# ItsyBitsy_Expander_v1_1.net
KiCad netlist of a schematic drawn in EAGLE
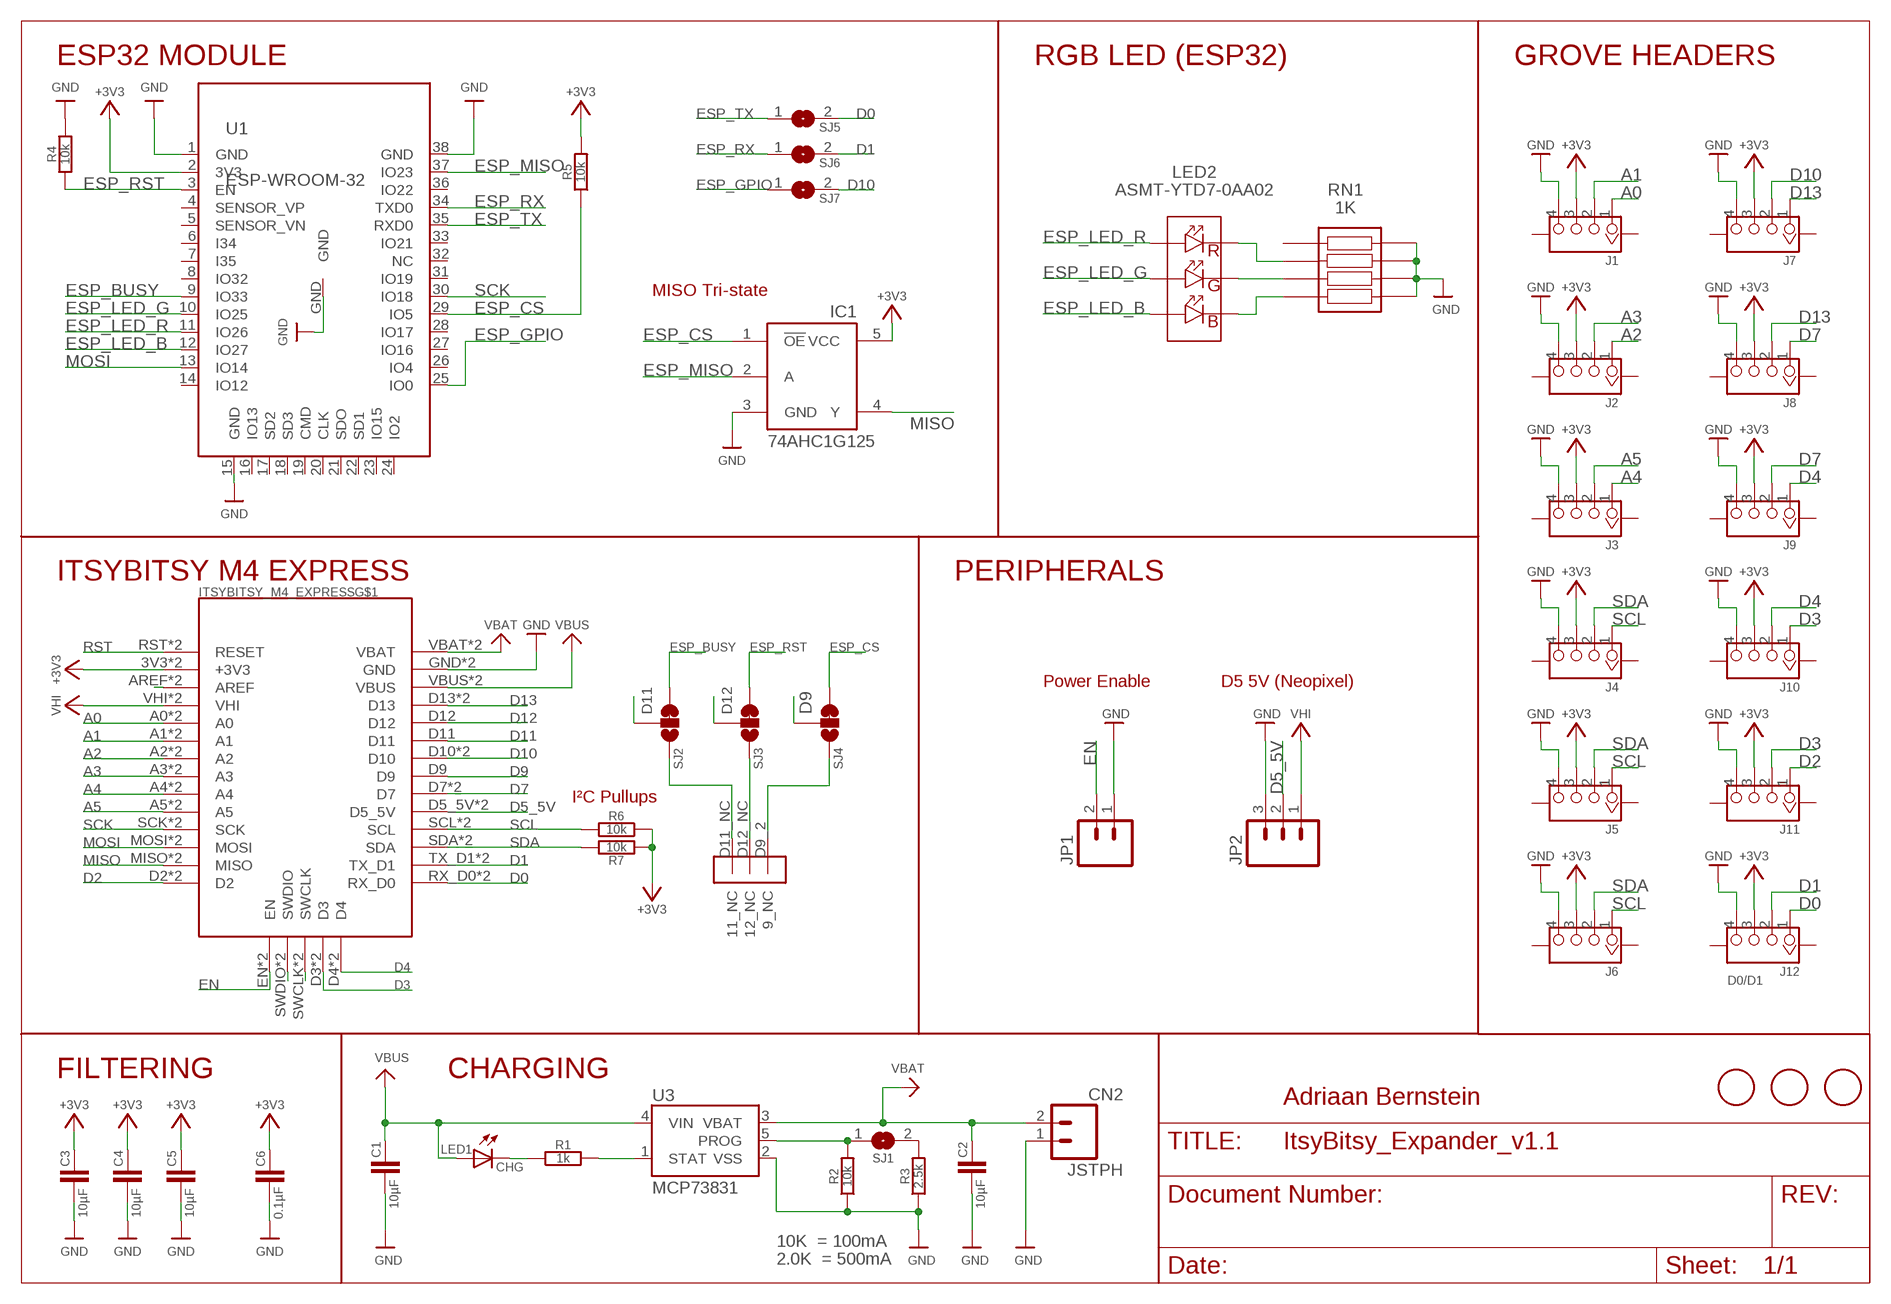
[diagram p0: schematic, sheet 1]

(export (version "E")
  (design (tool "Eeschema 10.0.6"))
  (components
    (comp (ref "C1")
      (value "10µF")
      (footprint "eagle-import:C0805")
      (libsource (lib "eagle-import") (part "C-EUC0805"))
    )
    (comp (ref "C2")
      (value "10µF")
      (footprint "eagle-import:C0805")
      (libsource (lib "eagle-import") (part "C-EUC0805"))
    )
    (comp (ref "C3")
      (value "10µF")
      (footprint "eagle-import:C0805")
      (libsource (lib "eagle-import") (part "C-EUC0805"))
    )
    (comp (ref "C4")
      (value "10µF")
      (footprint "eagle-import:C0805")
      (libsource (lib "eagle-import") (part "C-EUC0805"))
    )
    (comp (ref "C5")
      (value "10µF")
      (footprint "eagle-import:C0805")
      (libsource (lib "eagle-import") (part "C-EUC0805"))
    )
    (comp (ref "C6")
      (value "0.1µF")
      (footprint "eagle-import:C0603")
      (libsource (lib "eagle-import") (part "C-EUC0603"))
    )
    (comp (ref "CN2")
      (value "JSTPH")
      (footprint "eagle-import:JST-2-SMD")
      (libsource (lib "eagle-import") (part "M02-JST-2MM-SMT"))
    )
    (comp (ref "IC1")
      (value "74AHC1G125")
      (footprint "eagle-import:SOT23-5L")
      (libsource (lib "eagle-import") (part "74AHC1G125"))
    )
    (comp (ref "ITSYBITSY_M4_EXPRESS")
      (value "ITSYBITSY_M4_NC")
      (footprint "eagle-import:ITSYBITSY_M4_MIXED_DOUBLEHEADERS_ALL_NC")
      (libsource (lib "eagle-import") (part "ITSYBITSY_M4_NC"))
    )
    (comp (ref "J1")
      (value "H4P-SMD-2.0")
      (footprint "eagle-import:HW4-PTH-2.0")
      (libsource (lib "eagle-import") (part "GROVE-CONNECTOR-4PINHW4-PTH-2.0"))
    )
    (comp (ref "J2")
      (value "H4P-SMD-2.0")
      (footprint "eagle-import:HW4-PTH-2.0")
      (libsource (lib "eagle-import") (part "GROVE-CONNECTOR-4PINHW4-PTH-2.0"))
    )
    (comp (ref "J3")
      (value "H4P-SMD-2.0")
      (footprint "eagle-import:HW4-PTH-2.0")
      (libsource (lib "eagle-import") (part "GROVE-CONNECTOR-4PINHW4-PTH-2.0"))
    )
    (comp (ref "J4")
      (value "H4P-SMD-2.0")
      (footprint "eagle-import:HW4-PTH-2.0")
      (libsource (lib "eagle-import") (part "GROVE-CONNECTOR-4PINHW4-PTH-2.0"))
    )
    (comp (ref "J5")
      (value "H4P-SMD-2.0")
      (footprint "eagle-import:HW4-PTH-2.0")
      (libsource (lib "eagle-import") (part "GROVE-CONNECTOR-4PINHW4-PTH-2.0"))
    )
    (comp (ref "J6")
      (value "H4P-SMD-2.0")
      (footprint "eagle-import:HW4-PTH-2.0")
      (libsource (lib "eagle-import") (part "GROVE-CONNECTOR-4PINHW4-PTH-2.0"))
    )
    (comp (ref "J7")
      (value "H4P-SMD-2.0")
      (footprint "eagle-import:HW4-PTH-2.0")
      (libsource (lib "eagle-import") (part "GROVE-CONNECTOR-4PINHW4-PTH-2.0"))
    )
    (comp (ref "J8")
      (value "H4P-SMD-2.0")
      (footprint "eagle-import:HW4-PTH-2.0")
      (libsource (lib "eagle-import") (part "GROVE-CONNECTOR-4PINHW4-PTH-2.0"))
    )
    (comp (ref "J9")
      (value "H4P-SMD-2.0")
      (footprint "eagle-import:HW4-PTH-2.0")
      (libsource (lib "eagle-import") (part "GROVE-CONNECTOR-4PINHW4-PTH-2.0"))
    )
    (comp (ref "J10")
      (value "H4P-SMD-2.0")
      (footprint "eagle-import:HW4-PTH-2.0")
      (libsource (lib "eagle-import") (part "GROVE-CONNECTOR-4PINHW4-PTH-2.0"))
    )
    (comp (ref "J11")
      (value "H4P-SMD-2.0")
      (footprint "eagle-import:HW4-PTH-2.0")
      (libsource (lib "eagle-import") (part "GROVE-CONNECTOR-4PINHW4-PTH-2.0"))
    )
    (comp (ref "J12")
      (value "H4P-SMD-2.0")
      (footprint "eagle-import:HW4-PTH-2.0")
      (libsource (lib "eagle-import") (part "GROVE-CONNECTOR-4PINHW4-PTH-2.0"))
    )
    (comp (ref "JP1")
      (value "M02PTH")
      (footprint "eagle-import:1X02")
      (libsource (lib "eagle-import") (part "M02PTH"))
    )
    (comp (ref "JP2")
      (value "M03PTH")
      (footprint "eagle-import:1X03")
      (libsource (lib "eagle-import") (part "M03PTH"))
    )
    (comp (ref "LED1")
      (value "CHG")
      (footprint "eagle-import:CHIP-LED0603")
      (libsource (lib "eagle-import") (part "LEDCHIP-LED0603"))
    )
    (comp (ref "LED2")
      (value "ASMT-YTD7-0AA02")
      (footprint "eagle-import:ASMTYTD70AA02")
      (fields (field (name "MOUSER_PART_NUMBER") "630-ASMT-YTD7-0AA02"))
      (libsource (lib "eagle-import") (part "ASMT-YTD7-0AA02"))
    )
    (comp (ref "R1")
      (value "1k")
      (footprint "eagle-import:R0603")
      (libsource (lib "eagle-import") (part "R-EU_R0603"))
    )
    (comp (ref "R2")
      (value "10k")
      (footprint "eagle-import:R0603")
      (libsource (lib "eagle-import") (part "R-EU_R0603"))
    )
    (comp (ref "R3")
      (value "2.5k")
      (footprint "eagle-import:R0603")
      (libsource (lib "eagle-import") (part "R-EU_R0603"))
    )
    (comp (ref "R4")
      (value "10k")
      (footprint "eagle-import:R0603")
      (libsource (lib "eagle-import") (part "R-EU_R0603"))
    )
    (comp (ref "R5")
      (value "10k")
      (footprint "eagle-import:R0603")
      (libsource (lib "eagle-import") (part "R-EU_R0603"))
    )
    (comp (ref "R6")
      (value "10k")
      (footprint "eagle-import:R0603")
      (libsource (lib "eagle-import") (part "R-EU_R0603"))
    )
    (comp (ref "R7")
      (value "10k")
      (footprint "eagle-import:R0603")
      (libsource (lib "eagle-import") (part "R-EU_R0603"))
    )
    (comp (ref "RN1")
      (value "1K")
      (footprint "eagle-import:CAY1647R0F4LF")
      (fields
        (field (name "MANUFACTURER_PART_NUMBER") "CAY16-221J4AS")
        (field (name "MOUSER_PART_NUMBER") "652-CAY16-221J4AS")
      )
      (libsource (lib "eagle-import") (part "CAY16-221J4AS"))
    )
    (comp (ref "SJ1") (value "SJ") (footprint "eagle-import:SJ") (libsource (lib "eagle-import") (part "SJ")))
    (comp (ref "SJ5") (value "SJ") (footprint "eagle-import:SJ") (libsource (lib "eagle-import") (part "SJ")))
    (comp (ref "SJ6") (value "SJ") (footprint "eagle-import:SJ") (libsource (lib "eagle-import") (part "SJ")))
    (comp (ref "SJ7") (value "SJ") (footprint "eagle-import:SJ") (libsource (lib "eagle-import") (part "SJ")))
    (comp (ref "SJ_D11")
      (value "SJ2")
      (footprint "eagle-import:SJ_2WAY_CLOSED")
      (libsource (lib "eagle-import") (part "SJ_2WAY_CLOSED"))
    )
    (comp (ref "SJ_D12")
      (value "SJ3")
      (footprint "eagle-import:SJ_2WAY_CLOSED")
      (libsource (lib "eagle-import") (part "SJ_2WAY_CLOSED"))
    )
    (comp (ref "SJ_D13")
      (value "SJ4")
      (footprint "eagle-import:SJ_2WAY_CLOSED")
      (libsource (lib "eagle-import") (part "SJ_2WAY_CLOSED"))
    )
    (comp (ref "U$23")
      (value "FIDUCIAL")
      (footprint "eagle-import:FIDUCIAL_1MM")
      (libsource (lib "eagle-import") (part "FIDUCIAL"))
    )
    (comp (ref "U$35")
      (value "FIDUCIAL")
      (footprint "eagle-import:FIDUCIAL_1MM")
      (libsource (lib "eagle-import") (part "FIDUCIAL"))
    )
    (comp (ref "U$36")
      (value "FIDUCIAL")
      (footprint "eagle-import:FIDUCIAL_1MM")
      (libsource (lib "eagle-import") (part "FIDUCIAL"))
    )
    (comp (ref "U1")
      (value "ESP-WROOM-32")
      (footprint "eagle-import:ESP-WROOM-32")
      (libsource (lib "eagle-import") (part "ESP-WROOM-32"))
    )
    (comp (ref "U3")
      (value "MCP73831")
      (footprint "eagle-import:SOT23-5")
      (libsource (lib "eagle-import") (part "MCP73831"))
    )
  )
  (nets
    (net (code "1") (name "+3V3") (class "Default")
      (node (ref "C3") (pin "1") (pinfunction "1_1") (pintype "passive"))
      (node (ref "C4") (pin "1") (pinfunction "1_1") (pintype "passive"))
      (node (ref "C5") (pin "1") (pinfunction "1_1") (pintype "passive"))
      (node (ref "C6") (pin "1") (pinfunction "1_1") (pintype "passive"))
      (node (ref "IC1") (pin "5") (pinfunction "VCC_5") (pintype "power_in"))
      (node (ref "ITSYBITSY_M4_EXPRESS") (pin "3V3") (pinfunction "+3V3_3V3") (pintype "bidirectional"))
      (node (ref "ITSYBITSY_M4_EXPRESS") (pin "3V3_2") (pinfunction "+3V3_3V3_2") (pintype "bidirectional"))
      (node (ref "J1") (pin "3") (pinfunction "3_3") (pintype "bidirectional"))
      (node (ref "J10") (pin "3") (pinfunction "3_3") (pintype "bidirectional"))
      (node (ref "J11") (pin "3") (pinfunction "3_3") (pintype "bidirectional"))
      (node (ref "J12") (pin "3") (pinfunction "3_3") (pintype "bidirectional"))
      (node (ref "J2") (pin "3") (pinfunction "3_3") (pintype "bidirectional"))
      (node (ref "J3") (pin "3") (pinfunction "3_3") (pintype "bidirectional"))
      (node (ref "J4") (pin "3") (pinfunction "3_3") (pintype "bidirectional"))
      (node (ref "J5") (pin "3") (pinfunction "3_3") (pintype "bidirectional"))
      (node (ref "J6") (pin "3") (pinfunction "3_3") (pintype "bidirectional"))
      (node (ref "J7") (pin "3") (pinfunction "3_3") (pintype "bidirectional"))
      (node (ref "J8") (pin "3") (pinfunction "3_3") (pintype "bidirectional"))
      (node (ref "J9") (pin "3") (pinfunction "3_3") (pintype "bidirectional"))
      (node (ref "R5") (pin "2") (pinfunction "2_2") (pintype "passive"))
      (node (ref "R6") (pin "1") (pinfunction "1_1") (pintype "passive"))
      (node (ref "R7") (pin "1") (pinfunction "1_1") (pintype "passive"))
      (node (ref "U1") (pin "2") (pinfunction "3V3_2") (pintype "bidirectional"))
    )
    (net (code "2") (name "/A0") (class "Default")
      (node (ref "ITSYBITSY_M4_EXPRESS") (pin "A0") (pinfunction "A0_A0") (pintype "bidirectional"))
      (node (ref "ITSYBITSY_M4_EXPRESS") (pin "A0_2") (pinfunction "A0_A0_2") (pintype "bidirectional"))
      (node (ref "J1") (pin "1") (pinfunction "1_1") (pintype "bidirectional"))
    )
    (net (code "3") (name "/A1") (class "Default")
      (node (ref "ITSYBITSY_M4_EXPRESS") (pin "A1") (pinfunction "A1_A1") (pintype "bidirectional"))
      (node (ref "ITSYBITSY_M4_EXPRESS") (pin "A1_2") (pinfunction "A1_A1_2") (pintype "bidirectional"))
      (node (ref "J1") (pin "2") (pinfunction "2_2") (pintype "bidirectional"))
    )
    (net (code "4") (name "/A2") (class "Default")
      (node (ref "ITSYBITSY_M4_EXPRESS") (pin "A2") (pinfunction "A2_A2") (pintype "bidirectional"))
      (node (ref "ITSYBITSY_M4_EXPRESS") (pin "A2_2") (pinfunction "A2_A2_2") (pintype "bidirectional"))
      (node (ref "J2") (pin "1") (pinfunction "1_1") (pintype "bidirectional"))
    )
    (net (code "5") (name "/A3") (class "Default")
      (node (ref "ITSYBITSY_M4_EXPRESS") (pin "A3") (pinfunction "A3_A3") (pintype "bidirectional"))
      (node (ref "ITSYBITSY_M4_EXPRESS") (pin "A3_3") (pinfunction "A3_A3_3") (pintype "bidirectional"))
      (node (ref "J2") (pin "2") (pinfunction "2_2") (pintype "bidirectional"))
    )
    (net (code "6") (name "/A4") (class "Default")
      (node (ref "ITSYBITSY_M4_EXPRESS") (pin "A4") (pinfunction "A4_A4") (pintype "bidirectional"))
      (node (ref "ITSYBITSY_M4_EXPRESS") (pin "A4_2") (pinfunction "A4_A4_2") (pintype "bidirectional"))
      (node (ref "J3") (pin "1") (pinfunction "1_1") (pintype "bidirectional"))
    )
    (net (code "7") (name "/A5") (class "Default")
      (node (ref "ITSYBITSY_M4_EXPRESS") (pin "A5") (pinfunction "A5_A5") (pintype "bidirectional"))
      (node (ref "ITSYBITSY_M4_EXPRESS") (pin "A5_2") (pinfunction "A5_A5_2") (pintype "bidirectional"))
      (node (ref "J3") (pin "2") (pinfunction "2_2") (pintype "bidirectional"))
    )
    (net (code "8") (name "/D0") (class "Default")
      (node (ref "ITSYBITSY_M4_EXPRESS") (pin "RX_D0") (pinfunction "RX_D0_RX_D0") (pintype "bidirectional"))
      (node (ref "ITSYBITSY_M4_EXPRESS") (pin "RX_D0_2") (pinfunction "RX_D0_RX_D0_2") (pintype "bidirectional"))
      (node (ref "J12") (pin "1") (pinfunction "1_1") (pintype "bidirectional"))
      (node (ref "SJ5") (pin "2") (pinfunction "2_2") (pintype "passive"))
    )
    (net (code "9") (name "/D1") (class "Default")
      (node (ref "ITSYBITSY_M4_EXPRESS") (pin "TX_D1") (pinfunction "TX_D1_TX_D1") (pintype "bidirectional"))
      (node (ref "ITSYBITSY_M4_EXPRESS") (pin "TX_D1_2") (pinfunction "TX_D1_TX_D1_2") (pintype "bidirectional"))
      (node (ref "J12") (pin "2") (pinfunction "2_2") (pintype "bidirectional"))
      (node (ref "SJ6") (pin "2") (pinfunction "2_2") (pintype "passive"))
    )
    (net (code "10") (name "/D2") (class "Default")
      (node (ref "ITSYBITSY_M4_EXPRESS") (pin "D2") (pinfunction "D2_D2") (pintype "bidirectional"))
      (node (ref "ITSYBITSY_M4_EXPRESS") (pin "D2_2") (pinfunction "D2_D2_2") (pintype "bidirectional"))
      (node (ref "J11") (pin "1") (pinfunction "1_1") (pintype "bidirectional"))
    )
    (net (code "11") (name "/D3") (class "Default")
      (node (ref "ITSYBITSY_M4_EXPRESS") (pin "D3") (pinfunction "D3_D3") (pintype "bidirectional"))
      (node (ref "ITSYBITSY_M4_EXPRESS") (pin "D3_2") (pinfunction "D3_D3_2") (pintype "bidirectional"))
      (node (ref "J10") (pin "1") (pinfunction "1_1") (pintype "bidirectional"))
      (node (ref "J11") (pin "2") (pinfunction "2_2") (pintype "bidirectional"))
    )
    (net (code "12") (name "/D4") (class "Default")
      (node (ref "ITSYBITSY_M4_EXPRESS") (pin "D4") (pinfunction "D4_D4") (pintype "bidirectional"))
      (node (ref "ITSYBITSY_M4_EXPRESS") (pin "D4_2") (pinfunction "D4_D4_2") (pintype "bidirectional"))
      (node (ref "J10") (pin "2") (pinfunction "2_2") (pintype "bidirectional"))
      (node (ref "J9") (pin "1") (pinfunction "1_1") (pintype "bidirectional"))
    )
    (net (code "13") (name "/D5_5V") (class "Default")
      (node (ref "ITSYBITSY_M4_EXPRESS") (pin "D5_5V") (pinfunction "D5_5V_D5_5V") (pintype "bidirectional"))
      (node (ref "ITSYBITSY_M4_EXPRESS") (pin "D5_5V_2") (pinfunction "D5_5V_D5_5V_2") (pintype "bidirectional"))
      (node (ref "JP2") (pin "2") (pinfunction "2_2") (pintype "passive"))
    )
    (net (code "14") (name "/D7") (class "Default")
      (node (ref "ITSYBITSY_M4_EXPRESS") (pin "D7") (pinfunction "D7_D7") (pintype "bidirectional"))
      (node (ref "ITSYBITSY_M4_EXPRESS") (pin "D7_2") (pinfunction "D7_D7_2") (pintype "bidirectional"))
      (node (ref "J8") (pin "1") (pinfunction "1_1") (pintype "bidirectional"))
      (node (ref "J9") (pin "2") (pinfunction "2_2") (pintype "bidirectional"))
    )
    (net (code "15") (name "/D9") (class "Default")
      (node (ref "ITSYBITSY_M4_EXPRESS") (pin "D9") (pinfunction "D9_D9") (pintype "bidirectional"))
      (node (ref "SJ_D13") (pin "2") (pinfunction "2_2") (pintype "passive"))
    )
    (net (code "16") (name "/D10") (class "Default")
      (node (ref "ITSYBITSY_M4_EXPRESS") (pin "D10") (pinfunction "D10_D10") (pintype "bidirectional"))
      (node (ref "ITSYBITSY_M4_EXPRESS") (pin "D10_2") (pinfunction "D10_D10_2") (pintype "bidirectional"))
      (node (ref "J7") (pin "2") (pinfunction "2_2") (pintype "bidirectional"))
      (node (ref "SJ7") (pin "2") (pinfunction "2_2") (pintype "passive"))
    )
    (net (code "17") (name "/D11") (class "Default")
      (node (ref "ITSYBITSY_M4_EXPRESS") (pin "D11") (pinfunction "D11_D11") (pintype "bidirectional"))
      (node (ref "SJ_D11") (pin "2") (pinfunction "2_2") (pintype "passive"))
    )
    (net (code "18") (name "/D12") (class "Default")
      (node (ref "ITSYBITSY_M4_EXPRESS") (pin "D12") (pinfunction "D12_D12") (pintype "bidirectional"))
      (node (ref "SJ_D12") (pin "2") (pinfunction "2_2") (pintype "passive"))
    )
    (net (code "19") (name "/D13") (class "Default")
      (node (ref "ITSYBITSY_M4_EXPRESS") (pin "D13") (pinfunction "D13_D13") (pintype "bidirectional"))
      (node (ref "ITSYBITSY_M4_EXPRESS") (pin "D13_NC") (pinfunction "D13_D13_NC") (pintype "bidirectional"))
      (node (ref "J7") (pin "1") (pinfunction "1_1") (pintype "bidirectional"))
      (node (ref "J8") (pin "2") (pinfunction "2_2") (pintype "bidirectional"))
    )
    (net (code "20") (name "/EN") (class "Default")
      (node (ref "ITSYBITSY_M4_EXPRESS") (pin "EN") (pinfunction "EN_EN") (pintype "bidirectional"))
      (node (ref "ITSYBITSY_M4_EXPRESS") (pin "EN_2") (pinfunction "EN_EN_2") (pintype "bidirectional"))
      (node (ref "JP1") (pin "2") (pinfunction "2_2") (pintype "passive"))
    )
    (net (code "21") (name "/ESP_BUSY") (class "Default")
      (node (ref "SJ_D11") (pin "1") (pinfunction "1_1") (pintype "passive"))
      (node (ref "U1") (pin "9") (pinfunction "IO33_9") (pintype "bidirectional"))
    )
    (net (code "22") (name "/ESP_CS") (class "Default")
      (node (ref "IC1") (pin "1") (pinfunction "~{OE}_1") (pintype "input"))
      (node (ref "R5") (pin "1") (pinfunction "1_1") (pintype "passive"))
      (node (ref "SJ_D13") (pin "1") (pinfunction "1_1") (pintype "passive"))
      (node (ref "U1") (pin "29") (pinfunction "IO5_29") (pintype "bidirectional"))
    )
    (net (code "23") (name "/ESP_GPIO") (class "Default")
      (node (ref "SJ7") (pin "1") (pinfunction "1_1") (pintype "passive"))
      (node (ref "U1") (pin "25") (pinfunction "IO0_25") (pintype "bidirectional"))
    )
    (net (code "24") (name "/ESP_LED_B") (class "Default")
      (node (ref "LED2") (pin "6") (pinfunction "A_BLUE_6") (pintype "bidirectional"))
      (node (ref "U1") (pin "12") (pinfunction "IO27_12") (pintype "bidirectional"))
    )
    (net (code "25") (name "/ESP_LED_G") (class "Default")
      (node (ref "LED2") (pin "5") (pinfunction "A_GREEN_5") (pintype "bidirectional"))
      (node (ref "U1") (pin "10") (pinfunction "IO25_10") (pintype "bidirectional"))
    )
    (net (code "26") (name "/ESP_LED_R") (class "Default")
      (node (ref "LED2") (pin "4") (pinfunction "A_RED_4") (pintype "bidirectional"))
      (node (ref "U1") (pin "11") (pinfunction "IO26_11") (pintype "bidirectional"))
    )
    (net (code "27") (name "/ESP_MISO") (class "Default")
      (node (ref "IC1") (pin "2") (pinfunction "A_2") (pintype "input"))
      (node (ref "U1") (pin "37") (pinfunction "IO23_37") (pintype "bidirectional"))
    )
    (net (code "28") (name "/ESP_RST") (class "Default")
      (node (ref "R4") (pin "1") (pinfunction "1_1") (pintype "passive"))
      (node (ref "SJ_D12") (pin "1") (pinfunction "1_1") (pintype "passive"))
      (node (ref "U1") (pin "3") (pinfunction "EN_3") (pintype "bidirectional"))
    )
    (net (code "29") (name "/ESP_RX") (class "Default")
      (node (ref "SJ6") (pin "1") (pinfunction "1_1") (pintype "passive"))
      (node (ref "U1") (pin "34") (pinfunction "TXD0_34") (pintype "bidirectional"))
    )
    (net (code "30") (name "/ESP_TX") (class "Default")
      (node (ref "SJ5") (pin "1") (pinfunction "1_1") (pintype "passive"))
      (node (ref "U1") (pin "35") (pinfunction "RXD0_35") (pintype "bidirectional"))
    )
    (net (code "31") (name "/MISO") (class "Default")
      (node (ref "IC1") (pin "4") (pinfunction "Y_4") (pintype "output"))
      (node (ref "ITSYBITSY_M4_EXPRESS") (pin "MISO") (pinfunction "MISO_MISO") (pintype "bidirectional"))
      (node (ref "ITSYBITSY_M4_EXPRESS") (pin "MISO_2") (pinfunction "MISO_MISO_2") (pintype "bidirectional"))
    )
    (net (code "32") (name "/MOSI") (class "Default")
      (node (ref "ITSYBITSY_M4_EXPRESS") (pin "MOSI") (pinfunction "MOSI_MOSI") (pintype "bidirectional"))
      (node (ref "ITSYBITSY_M4_EXPRESS") (pin "MOSI_2") (pinfunction "MOSI_MOSI_2") (pintype "bidirectional"))
      (node (ref "U1") (pin "13") (pinfunction "IO14_13") (pintype "bidirectional"))
    )
    (net (code "33") (name "/RST") (class "Default")
      (node (ref "ITSYBITSY_M4_EXPRESS") (pin "RST") (pinfunction "RESET_RST") (pintype "bidirectional"))
      (node (ref "ITSYBITSY_M4_EXPRESS") (pin "RST_2") (pinfunction "RESET_RST_2") (pintype "bidirectional"))
    )
    (net (code "34") (name "/SCK") (class "Default")
      (node (ref "ITSYBITSY_M4_EXPRESS") (pin "SCK") (pinfunction "SCK_SCK") (pintype "bidirectional"))
      (node (ref "ITSYBITSY_M4_EXPRESS") (pin "SCK_2") (pinfunction "SCK_SCK_2") (pintype "bidirectional"))
      (node (ref "U1") (pin "30") (pinfunction "IO18_30") (pintype "bidirectional"))
    )
    (net (code "35") (name "/SCL") (class "Default")
      (node (ref "ITSYBITSY_M4_EXPRESS") (pin "SCL") (pinfunction "SCL_SCL") (pintype "bidirectional"))
      (node (ref "ITSYBITSY_M4_EXPRESS") (pin "SCL_2") (pinfunction "SCL_SCL_2") (pintype "bidirectional"))
      (node (ref "J4") (pin "1") (pinfunction "1_1") (pintype "bidirectional"))
      (node (ref "J5") (pin "1") (pinfunction "1_1") (pintype "bidirectional"))
      (node (ref "J6") (pin "1") (pinfunction "1_1") (pintype "bidirectional"))
      (node (ref "R6") (pin "2") (pinfunction "2_2") (pintype "passive"))
    )
    (net (code "36") (name "/SDA") (class "Default")
      (node (ref "ITSYBITSY_M4_EXPRESS") (pin "SDA") (pinfunction "SDA_SDA") (pintype "bidirectional"))
      (node (ref "ITSYBITSY_M4_EXPRESS") (pin "SDA_2") (pinfunction "SDA_SDA_2") (pintype "bidirectional"))
      (node (ref "J4") (pin "2") (pinfunction "2_2") (pintype "bidirectional"))
      (node (ref "J5") (pin "2") (pinfunction "2_2") (pintype "bidirectional"))
      (node (ref "J6") (pin "2") (pinfunction "2_2") (pintype "bidirectional"))
      (node (ref "R7") (pin "2") (pinfunction "2_2") (pintype "passive"))
    )
    (net (code "37") (name "GND") (class "Default")
      (node (ref "C1") (pin "2") (pinfunction "2_2") (pintype "passive"))
      (node (ref "C2") (pin "2") (pinfunction "2_2") (pintype "passive"))
      (node (ref "C3") (pin "2") (pinfunction "2_2") (pintype "passive"))
      (node (ref "C4") (pin "2") (pinfunction "2_2") (pintype "passive"))
      (node (ref "C5") (pin "2") (pinfunction "2_2") (pintype "passive"))
      (node (ref "C6") (pin "2") (pinfunction "2_2") (pintype "passive"))
      (node (ref "CN2") (pin "1") (pinfunction "1_1") (pintype "passive"))
      (node (ref "IC1") (pin "3") (pinfunction "GND_3") (pintype "power_in"))
      (node (ref "ITSYBITSY_M4_EXPRESS") (pin "GND") (pinfunction "GND_GND") (pintype "bidirectional"))
      (node (ref "ITSYBITSY_M4_EXPRESS") (pin "GND_2") (pinfunction "GND_GND_2") (pintype "bidirectional"))
      (node (ref "J1") (pin "4") (pinfunction "4_4") (pintype "bidirectional"))
      (node (ref "J10") (pin "4") (pinfunction "4_4") (pintype "bidirectional"))
      (node (ref "J11") (pin "4") (pinfunction "4_4") (pintype "bidirectional"))
      (node (ref "J12") (pin "4") (pinfunction "4_4") (pintype "bidirectional"))
      (node (ref "J2") (pin "4") (pinfunction "4_4") (pintype "bidirectional"))
      (node (ref "J3") (pin "4") (pinfunction "4_4") (pintype "bidirectional"))
      (node (ref "J4") (pin "4") (pinfunction "4_4") (pintype "bidirectional"))
      (node (ref "J5") (pin "4") (pinfunction "4_4") (pintype "bidirectional"))
      (node (ref "J6") (pin "4") (pinfunction "4_4") (pintype "bidirectional"))
      (node (ref "J7") (pin "4") (pinfunction "4_4") (pintype "bidirectional"))
      (node (ref "J8") (pin "4") (pinfunction "4_4") (pintype "bidirectional"))
      (node (ref "J9") (pin "4") (pinfunction "4_4") (pintype "bidirectional"))
      (node (ref "JP1") (pin "1") (pinfunction "1_1") (pintype "passive"))
      (node (ref "JP2") (pin "3") (pinfunction "3_3") (pintype "passive"))
      (node (ref "R2") (pin "1") (pinfunction "1_1") (pintype "passive"))
      (node (ref "R3") (pin "1") (pinfunction "1_1") (pintype "passive"))
      (node (ref "R4") (pin "2") (pinfunction "2_2") (pintype "passive"))
      (node (ref "RN1") (pin "5") (pinfunction "R4_2_5") (pintype "bidirectional"))
      (node (ref "RN1") (pin "6") (pinfunction "R3_2_6") (pintype "bidirectional"))
      (node (ref "RN1") (pin "7") (pinfunction "R2_2_7") (pintype "bidirectional"))
      (node (ref "RN1") (pin "8") (pinfunction "R1_2_8") (pintype "bidirectional"))
      (node (ref "U1") (pin "1") (pinfunction "GND_1") (pintype "bidirectional"))
      (node (ref "U1") (pin "15") (pinfunction "GND_15") (pintype "bidirectional"))
      (node (ref "U1") (pin "38") (pinfunction "GND_38") (pintype "bidirectional"))
      (node (ref "U1") (pin "GND") (pinfunction "GND_GND") (pintype "bidirectional"))
      (node (ref "U3") (pin "2") (pinfunction "VSS_2") (pintype "power_in"))
    )
    (net (code "38") (name "Net-(ITSYBITSY_M4_EXPRESS-PadAREF)") (class "Default")
      (node (ref "ITSYBITSY_M4_EXPRESS") (pin "AREF") (pinfunction "AREF_AREF") (pintype "bidirectional"))
      (node (ref "ITSYBITSY_M4_EXPRESS") (pin "AREF_2") (pinfunction "AREF_AREF_2") (pintype "bidirectional"))
    )
    (net (code "39") (name "Net-(ITSYBITSY_M4_EXPRESS-PadSWCLK)") (class "Default")
      (node (ref "ITSYBITSY_M4_EXPRESS") (pin "SWCLK") (pinfunction "SWCLK_SWCLK") (pintype "bidirectional"))
      (node (ref "ITSYBITSY_M4_EXPRESS") (pin "SWCLK_2") (pinfunction "SWCLK_SWCLK_2") (pintype "bidirectional"))
    )
    (net (code "40") (name "Net-(ITSYBITSY_M4_EXPRESS-PadSWDIO)") (class "Default")
      (node (ref "ITSYBITSY_M4_EXPRESS") (pin "SWDIO") (pinfunction "SWDIO_SWDIO") (pintype "bidirectional"))
      (node (ref "ITSYBITSY_M4_EXPRESS") (pin "SWDIO_2") (pinfunction "SWDIO_SWDIO_2") (pintype "bidirectional"))
    )
    (net (code "41") (name "Net-(ITSYBITSY_M4_EXPRESSB-9_NC)") (class "Default")
      (node (ref "ITSYBITSY_M4_EXPRESS") (pin "D9_2") (pinfunction "9_NC_D9_2") (pintype "bidirectional"))
      (node (ref "SJ_D13") (pin "3") (pinfunction "3_3") (pintype "passive"))
    )
    (net (code "42") (name "Net-(ITSYBITSY_M4_EXPRESSB-11_NC)") (class "Default")
      (node (ref "ITSYBITSY_M4_EXPRESS") (pin "D11_NC") (pinfunction "11_NC_D11_NC") (pintype "bidirectional"))
      (node (ref "SJ_D11") (pin "3") (pinfunction "3_3") (pintype "passive"))
    )
    (net (code "43") (name "Net-(ITSYBITSY_M4_EXPRESSB-12_NC)") (class "Default")
      (node (ref "ITSYBITSY_M4_EXPRESS") (pin "D12_NC") (pinfunction "12_NC_D12_NC") (pintype "bidirectional"))
      (node (ref "SJ_D12") (pin "3") (pinfunction "3_3") (pintype "passive"))
    )
    (net (code "44") (name "Net-(LED1-PadC)") (class "Default")
      (node (ref "LED1") (pin "C") (pinfunction "C_C") (pintype "passive"))
      (node (ref "R1") (pin "1") (pinfunction "1_1") (pintype "passive"))
    )
    (net (code "45") (name "Net-(LED2-K_BLUE)") (class "Default")
      (node (ref "LED2") (pin "1") (pinfunction "K_BLUE_1") (pintype "bidirectional"))
      (node (ref "RN1") (pin "4") (pinfunction "R4_1_4") (pintype "bidirectional"))
    )
    (net (code "46") (name "Net-(LED2-K_GREEN)") (class "Default")
      (node (ref "LED2") (pin "2") (pinfunction "K_GREEN_2") (pintype "bidirectional"))
      (node (ref "RN1") (pin "3") (pinfunction "R3_1_3") (pintype "bidirectional"))
    )
    (net (code "47") (name "Net-(LED2-K_RED)") (class "Default")
      (node (ref "LED2") (pin "3") (pinfunction "K_RED_3") (pintype "bidirectional"))
      (node (ref "RN1") (pin "2") (pinfunction "R2_1_2") (pintype "bidirectional"))
    )
    (net (code "48") (name "Net-(R3-Pad2)") (class "Default")
      (node (ref "R3") (pin "2") (pinfunction "2_2") (pintype "passive"))
      (node (ref "SJ1") (pin "2") (pinfunction "2_2") (pintype "passive"))
    )
    (net (code "49") (name "Net-(U3-PROG)") (class "Default")
      (node (ref "R2") (pin "2") (pinfunction "2_2") (pintype "passive"))
      (node (ref "SJ1") (pin "1") (pinfunction "1_1") (pintype "passive"))
      (node (ref "U3") (pin "5") (pinfunction "PROG_5") (pintype "input"))
    )
    (net (code "50") (name "Net-(U3-STAT)") (class "Default")
      (node (ref "R1") (pin "2") (pinfunction "2_2") (pintype "passive"))
      (node (ref "U3") (pin "1") (pinfunction "STAT_1") (pintype "output"))
    )
    (net (code "51") (name "VBAT") (class "Default")
      (node (ref "C2") (pin "1") (pinfunction "1_1") (pintype "passive"))
      (node (ref "CN2") (pin "2") (pinfunction "2_2") (pintype "passive"))
      (node (ref "ITSYBITSY_M4_EXPRESS") (pin "VBAT") (pinfunction "VBAT_VBAT") (pintype "bidirectional"))
      (node (ref "ITSYBITSY_M4_EXPRESS") (pin "VBAT_2") (pinfunction "VBAT_VBAT_2") (pintype "bidirectional"))
      (node (ref "U3") (pin "3") (pinfunction "VBAT_3") (pintype "power_in"))
    )
    (net (code "52") (name "VBUS") (class "Default")
      (node (ref "C1") (pin "1") (pinfunction "1_1") (pintype "passive"))
      (node (ref "ITSYBITSY_M4_EXPRESS") (pin "VBUS") (pinfunction "VBUS_VBUS") (pintype "bidirectional"))
      (node (ref "ITSYBITSY_M4_EXPRESS") (pin "VBUS_2") (pinfunction "VBUS_VBUS_2") (pintype "bidirectional"))
      (node (ref "LED1") (pin "A") (pinfunction "A_A") (pintype "passive"))
      (node (ref "U3") (pin "4") (pinfunction "VIN_4") (pintype "power_in"))
    )
    (net (code "53") (name "VHI") (class "Default")
      (node (ref "ITSYBITSY_M4_EXPRESS") (pin "VHI") (pinfunction "VHI_VHI") (pintype "bidirectional"))
      (node (ref "ITSYBITSY_M4_EXPRESS") (pin "VHI_2") (pinfunction "VHI_VHI_2") (pintype "bidirectional"))
      (node (ref "JP2") (pin "1") (pinfunction "1_1") (pintype "passive"))
    )
    (net (code "54") (name "unconnected-(J1-SS1-Pad5)") (class "Default")
      (node (ref "J1") (pin "5") (pinfunction "SS1_5") (pintype "bidirectional"))
    )
    (net (code "55") (name "unconnected-(J1-SS2-Pad6)") (class "Default")
      (node (ref "J1") (pin "6") (pinfunction "SS2_6") (pintype "bidirectional"))
    )
    (net (code "56") (name "unconnected-(J2-SS1-Pad5)") (class "Default")
      (node (ref "J2") (pin "5") (pinfunction "SS1_5") (pintype "bidirectional"))
    )
    (net (code "57") (name "unconnected-(J2-SS2-Pad6)") (class "Default")
      (node (ref "J2") (pin "6") (pinfunction "SS2_6") (pintype "bidirectional"))
    )
    (net (code "58") (name "unconnected-(J3-SS1-Pad5)") (class "Default")
      (node (ref "J3") (pin "5") (pinfunction "SS1_5") (pintype "bidirectional"))
    )
    (net (code "59") (name "unconnected-(J3-SS2-Pad6)") (class "Default")
      (node (ref "J3") (pin "6") (pinfunction "SS2_6") (pintype "bidirectional"))
    )
    (net (code "60") (name "unconnected-(J4-SS1-Pad5)") (class "Default")
      (node (ref "J4") (pin "5") (pinfunction "SS1_5") (pintype "bidirectional"))
    )
    (net (code "61") (name "unconnected-(J4-SS2-Pad6)") (class "Default")
      (node (ref "J4") (pin "6") (pinfunction "SS2_6") (pintype "bidirectional"))
    )
    (net (code "62") (name "unconnected-(J5-SS1-Pad5)") (class "Default")
      (node (ref "J5") (pin "5") (pinfunction "SS1_5") (pintype "bidirectional"))
    )
    (net (code "63") (name "unconnected-(J5-SS2-Pad6)") (class "Default")
      (node (ref "J5") (pin "6") (pinfunction "SS2_6") (pintype "bidirectional"))
    )
    (net (code "64") (name "unconnected-(J6-SS1-Pad5)") (class "Default")
      (node (ref "J6") (pin "5") (pinfunction "SS1_5") (pintype "bidirectional"))
    )
    (net (code "65") (name "unconnected-(J6-SS2-Pad6)") (class "Default")
      (node (ref "J6") (pin "6") (pinfunction "SS2_6") (pintype "bidirectional"))
    )
    (net (code "66") (name "unconnected-(J7-SS1-Pad5)") (class "Default")
      (node (ref "J7") (pin "5") (pinfunction "SS1_5") (pintype "bidirectional"))
    )
    (net (code "67") (name "unconnected-(J7-SS2-Pad6)") (class "Default")
      (node (ref "J7") (pin "6") (pinfunction "SS2_6") (pintype "bidirectional"))
    )
    (net (code "68") (name "unconnected-(J8-SS1-Pad5)") (class "Default")
      (node (ref "J8") (pin "5") (pinfunction "SS1_5") (pintype "bidirectional"))
    )
    (net (code "69") (name "unconnected-(J8-SS2-Pad6)") (class "Default")
      (node (ref "J8") (pin "6") (pinfunction "SS2_6") (pintype "bidirectional"))
    )
    (net (code "70") (name "unconnected-(J9-SS1-Pad5)") (class "Default")
      (node (ref "J9") (pin "5") (pinfunction "SS1_5") (pintype "bidirectional"))
    )
    (net (code "71") (name "unconnected-(J9-SS2-Pad6)") (class "Default")
      (node (ref "J9") (pin "6") (pinfunction "SS2_6") (pintype "bidirectional"))
    )
    (net (code "72") (name "unconnected-(J10-SS1-Pad5)") (class "Default")
      (node (ref "J10") (pin "5") (pinfunction "SS1_5") (pintype "bidirectional"))
    )
    (net (code "73") (name "unconnected-(J10-SS2-Pad6)") (class "Default")
      (node (ref "J10") (pin "6") (pinfunction "SS2_6") (pintype "bidirectional"))
    )
    (net (code "74") (name "unconnected-(J11-SS1-Pad5)") (class "Default")
      (node (ref "J11") (pin "5") (pinfunction "SS1_5") (pintype "bidirectional"))
    )
    (net (code "75") (name "unconnected-(J11-SS2-Pad6)") (class "Default")
      (node (ref "J11") (pin "6") (pinfunction "SS2_6") (pintype "bidirectional"))
    )
    (net (code "76") (name "unconnected-(J12-SS1-Pad5)") (class "Default")
      (node (ref "J12") (pin "5") (pinfunction "SS1_5") (pintype "bidirectional"))
    )
    (net (code "77") (name "unconnected-(J12-SS2-Pad6)") (class "Default")
      (node (ref "J12") (pin "6") (pinfunction "SS2_6") (pintype "bidirectional"))
    )
    (net (code "78") (name "unconnected-(RN1-R1_1-Pad1)") (class "Default")
      (node (ref "RN1") (pin "1") (pinfunction "R1_1_1") (pintype "bidirectional"))
    )
    (net (code "79") (name "unconnected-(U1-CLK-Pad20)") (class "Default")
      (node (ref "U1") (pin "20") (pinfunction "CLK_20") (pintype "bidirectional"))
    )
    (net (code "80") (name "unconnected-(U1-CMD-Pad19)") (class "Default")
      (node (ref "U1") (pin "19") (pinfunction "CMD_19") (pintype "bidirectional"))
    )
    (net (code "81") (name "unconnected-(U1-I34-Pad6)") (class "Default")
      (node (ref "U1") (pin "6") (pinfunction "I34_6") (pintype "input"))
    )
    (net (code "82") (name "unconnected-(U1-I35-Pad7)") (class "Default")
      (node (ref "U1") (pin "7") (pinfunction "I35_7") (pintype "input"))
    )
    (net (code "83") (name "unconnected-(U1-IO2-Pad24)") (class "Default")
      (node (ref "U1") (pin "24") (pinfunction "IO2_24") (pintype "bidirectional"))
    )
    (net (code "84") (name "unconnected-(U1-IO4-Pad26)") (class "Default")
      (node (ref "U1") (pin "26") (pinfunction "IO4_26") (pintype "bidirectional"))
    )
    (net (code "85") (name "unconnected-(U1-IO12-Pad14)") (class "Default")
      (node (ref "U1") (pin "14") (pinfunction "IO12_14") (pintype "bidirectional"))
    )
    (net (code "86") (name "unconnected-(U1-IO13-Pad16)") (class "Default")
      (node (ref "U1") (pin "16") (pinfunction "IO13_16") (pintype "bidirectional"))
    )
    (net (code "87") (name "unconnected-(U1-IO15-Pad23)") (class "Default")
      (node (ref "U1") (pin "23") (pinfunction "IO15_23") (pintype "bidirectional"))
    )
    (net (code "88") (name "unconnected-(U1-IO16-Pad27)") (class "Default")
      (node (ref "U1") (pin "27") (pinfunction "IO16_27") (pintype "bidirectional"))
    )
    (net (code "89") (name "unconnected-(U1-IO17-Pad28)") (class "Default")
      (node (ref "U1") (pin "28") (pinfunction "IO17_28") (pintype "bidirectional"))
    )
    (net (code "90") (name "unconnected-(U1-IO19-Pad31)") (class "Default")
      (node (ref "U1") (pin "31") (pinfunction "IO19_31") (pintype "bidirectional"))
    )
    (net (code "91") (name "unconnected-(U1-IO21-Pad33)") (class "Default")
      (node (ref "U1") (pin "33") (pinfunction "IO21_33") (pintype "bidirectional"))
    )
    (net (code "92") (name "unconnected-(U1-IO22-Pad36)") (class "Default")
      (node (ref "U1") (pin "36") (pinfunction "IO22_36") (pintype "bidirectional"))
    )
    (net (code "93") (name "unconnected-(U1-IO32-Pad8)") (class "Default")
      (node (ref "U1") (pin "8") (pinfunction "IO32_8") (pintype "bidirectional"))
    )
    (net (code "94") (name "unconnected-(U1-NC-Pad32)") (class "Default")
      (node (ref "U1") (pin "32") (pinfunction "NC_32") (pintype "bidirectional"))
    )
    (net (code "95") (name "unconnected-(U1-SD1-Pad22)") (class "Default")
      (node (ref "U1") (pin "22") (pinfunction "SD1_22") (pintype "bidirectional"))
    )
    (net (code "96") (name "unconnected-(U1-SD2-Pad17)") (class "Default")
      (node (ref "U1") (pin "17") (pinfunction "SD2_17") (pintype "bidirectional"))
    )
    (net (code "97") (name "unconnected-(U1-SD3-Pad18)") (class "Default")
      (node (ref "U1") (pin "18") (pinfunction "SD3_18") (pintype "bidirectional"))
    )
    (net (code "98") (name "unconnected-(U1-SDO-Pad21)") (class "Default")
      (node (ref "U1") (pin "21") (pinfunction "SDO_21") (pintype "bidirectional"))
    )
    (net (code "99") (name "unconnected-(U1-SENSOR_VN-Pad5)") (class "Default")
      (node (ref "U1") (pin "5") (pinfunction "SENSOR_VN_5") (pintype "input"))
    )
    (net (code "100") (name "unconnected-(U1-SENSOR_VP-Pad4)") (class "Default")
      (node (ref "U1") (pin "4") (pinfunction "SENSOR_VP_4") (pintype "input"))
    )
  )
)
